# BlackIce-Nxt.net
KiCad netlist of a schematic drawn in EAGLE
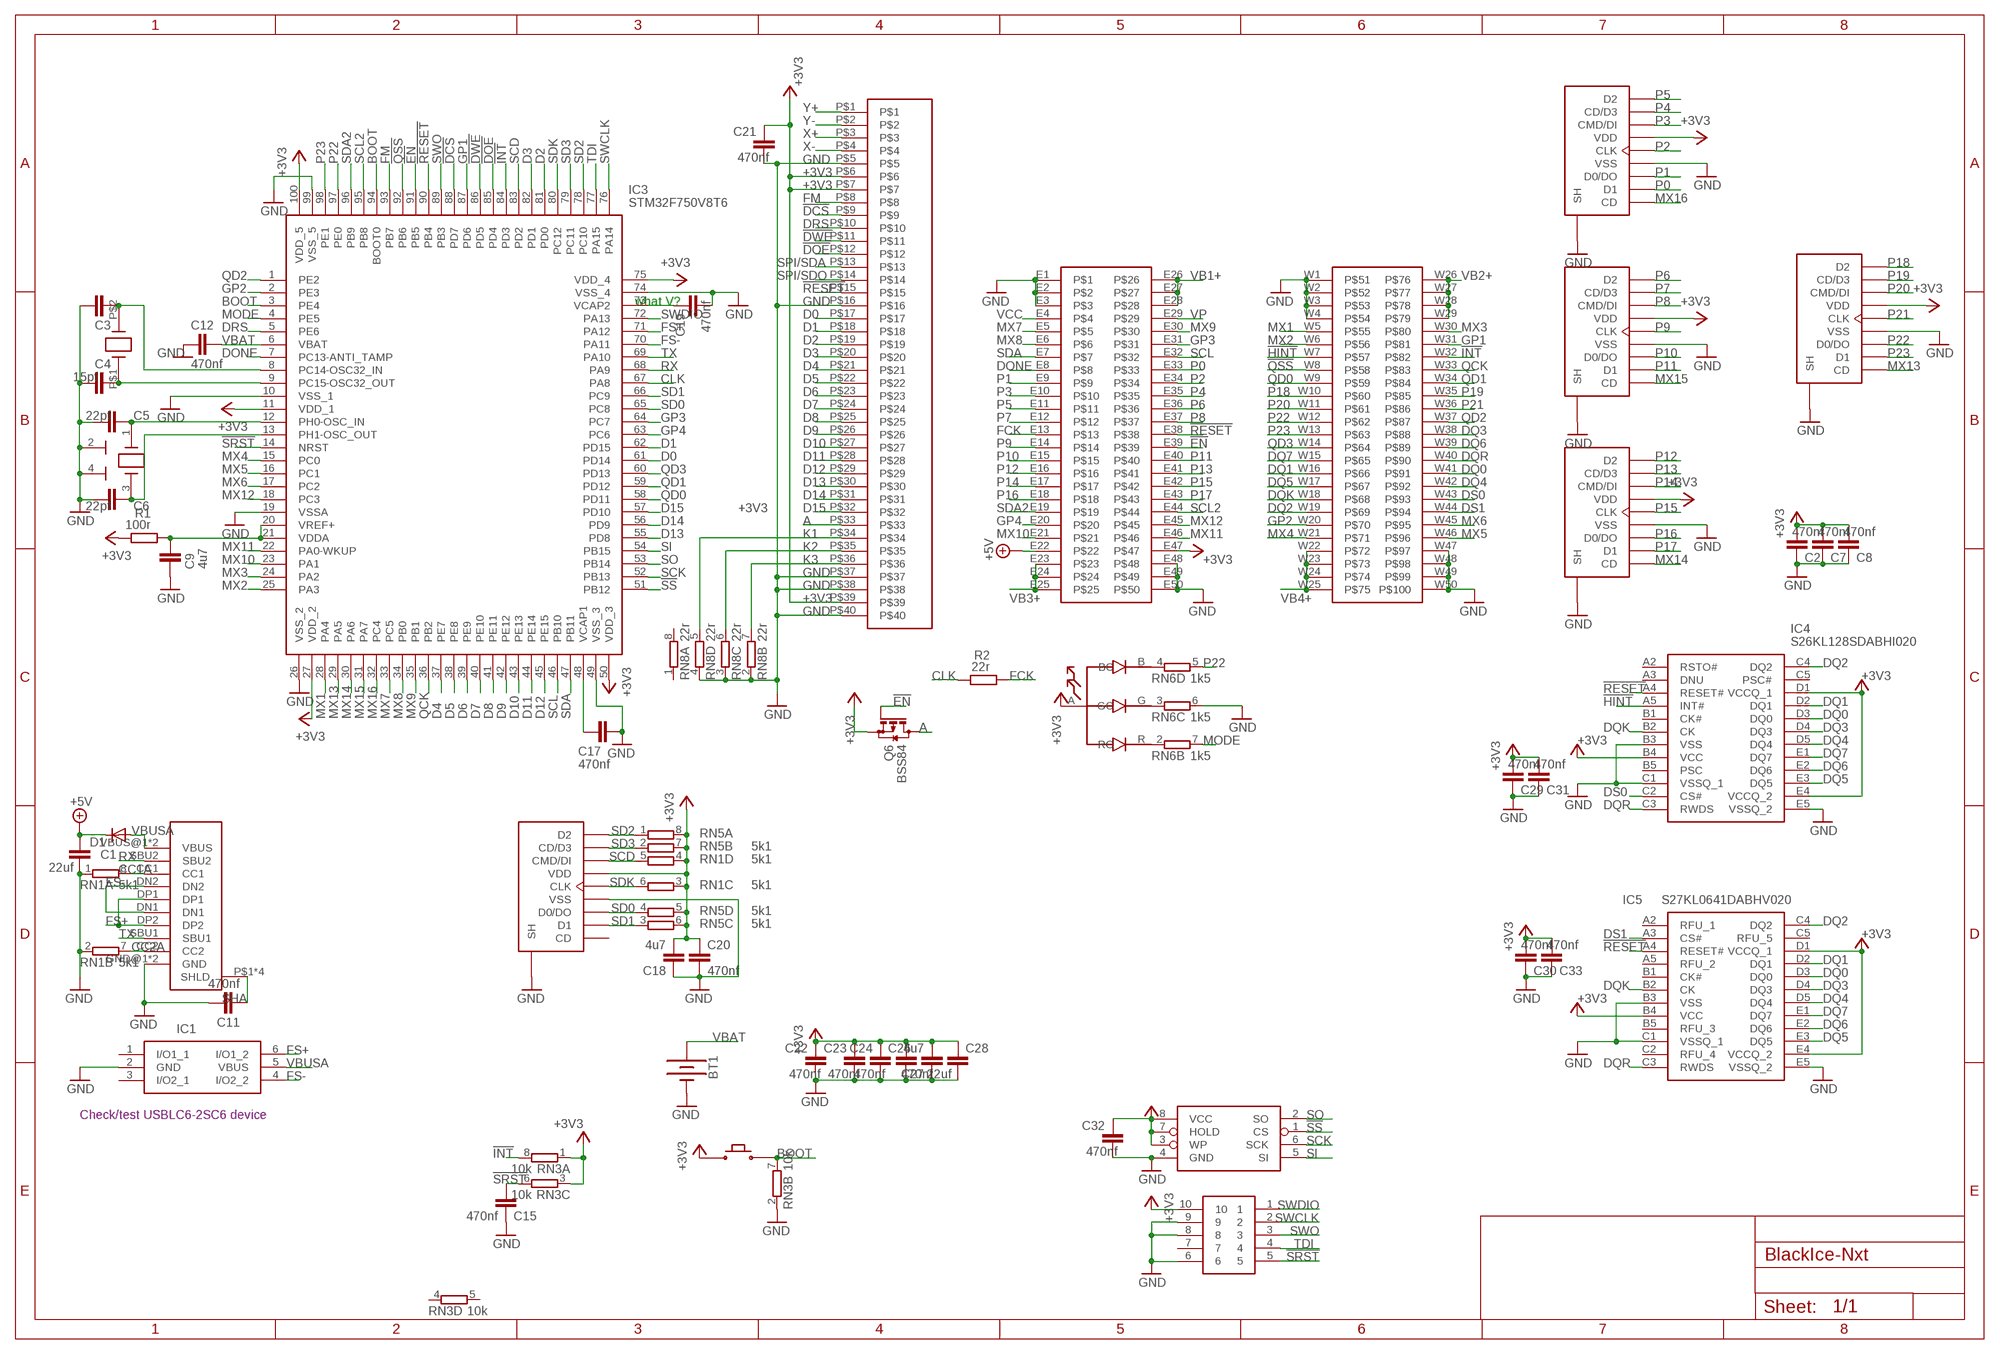
[diagram p0: schematic, sheet 1]

(export (version "E")
  (design (tool "Eeschema 10.0.6"))
  (components
    (comp (ref "B2")
      (value "4X3-RA-BUTTON")
      (footprint "eagle-import:4X3-RA-BUTTON")
      (libsource (lib "eagle-import") (part "4X3-RA-BUTTON"))
    )
    (comp (ref "BT1")
      (value "BATTERY-20MM_SMD")
      (footprint "eagle-import:BATTCON_20MM")
      (libsource (lib "eagle-import") (part "BATTERY-20MM_SMD"))
    )
    (comp (ref "C1")
      (value "22uf")
      (footprint "eagle-import:C0603")
      (libsource (lib "eagle-import") (part "C-EUC0603"))
    )
    (comp (ref "C2")
      (value "470nf")
      (footprint "eagle-import:C0402")
      (libsource (lib "eagle-import") (part "C-EUC0402"))
    )
    (comp (ref "C3")
      (value "15pf")
      (footprint "eagle-import:C0402")
      (libsource (lib "eagle-import") (part "C-EUC0402"))
    )
    (comp (ref "C4")
      (value "15pf")
      (footprint "eagle-import:C0402")
      (libsource (lib "eagle-import") (part "C-EUC0402"))
    )
    (comp (ref "C5")
      (value "22pf")
      (footprint "eagle-import:C0402")
      (libsource (lib "eagle-import") (part "C-EUC0402"))
    )
    (comp (ref "C6")
      (value "22pf")
      (footprint "eagle-import:C0402")
      (libsource (lib "eagle-import") (part "C-EUC0402"))
    )
    (comp (ref "C7")
      (value "470nf")
      (footprint "eagle-import:C0402")
      (libsource (lib "eagle-import") (part "C-EUC0402"))
    )
    (comp (ref "C8")
      (value "470nf")
      (footprint "eagle-import:C0402")
      (libsource (lib "eagle-import") (part "C-EUC0402"))
    )
    (comp (ref "C9")
      (value "4u7")
      (footprint "eagle-import:C0402")
      (libsource (lib "eagle-import") (part "C-EUC0402"))
    )
    (comp (ref "C10")
      (value "USB-C-16")
      (footprint "eagle-import:USB-C")
      (libsource (lib "eagle-import") (part "USB-C-16"))
    )
    (comp (ref "C11")
      (value "470nf")
      (footprint "eagle-import:C0402")
      (libsource (lib "eagle-import") (part "C-EUC0402"))
    )
    (comp (ref "C12")
      (value "470nf")
      (footprint "eagle-import:C0402")
      (libsource (lib "eagle-import") (part "C-EUC0402"))
    )
    (comp (ref "C15")
      (value "470nf")
      (footprint "eagle-import:C0402")
      (libsource (lib "eagle-import") (part "C-EUC0402"))
    )
    (comp (ref "C16")
      (value "TF-15X15")
      (footprint "eagle-import:SDCARD")
      (libsource (lib "eagle-import") (part "TF-15X15"))
    )
    (comp (ref "C17")
      (value "470nf")
      (footprint "eagle-import:C0402")
      (libsource (lib "eagle-import") (part "C-EUC0402"))
    )
    (comp (ref "C18")
      (value "4u7")
      (footprint "eagle-import:C0402")
      (libsource (lib "eagle-import") (part "C-EUC0402"))
    )
    (comp (ref "C19")
      (value "470nf")
      (footprint "eagle-import:C0402")
      (libsource (lib "eagle-import") (part "C-EUC0402"))
    )
    (comp (ref "C20")
      (value "470nf")
      (footprint "eagle-import:C0402")
      (libsource (lib "eagle-import") (part "C-EUC0402"))
    )
    (comp (ref "C21")
      (value "470nf")
      (footprint "eagle-import:C0402")
      (libsource (lib "eagle-import") (part "C-EUC0402"))
    )
    (comp (ref "C22")
      (value "470nf")
      (footprint "eagle-import:C0402")
      (libsource (lib "eagle-import") (part "C-EUC0402"))
    )
    (comp (ref "C23")
      (value "470nf")
      (footprint "eagle-import:C0402")
      (libsource (lib "eagle-import") (part "C-EUC0402"))
    )
    (comp (ref "C24")
      (value "470nf")
      (footprint "eagle-import:C0402")
      (libsource (lib "eagle-import") (part "C-EUC0402"))
    )
    (comp (ref "C25")
      (value "XF2M-4015-1AFPC-0.5")
      (footprint "eagle-import:XF2M-4015-1A")
      (libsource (lib "eagle-import") (part "XF2M-4015-1AFPC-0.5"))
    )
    (comp (ref "C26")
      (value "470nf")
      (footprint "eagle-import:C0402")
      (libsource (lib "eagle-import") (part "C-EUC0402"))
    )
    (comp (ref "C27")
      (value "4u7")
      (footprint "eagle-import:C0402")
      (libsource (lib "eagle-import") (part "C-EUC0402"))
    )
    (comp (ref "C28")
      (value "22uf")
      (footprint "eagle-import:C0603")
      (libsource (lib "eagle-import") (part "C-EUC0603"))
    )
    (comp (ref "C29")
      (value "470nf")
      (footprint "eagle-import:C0402")
      (libsource (lib "eagle-import") (part "C-EUC0402"))
    )
    (comp (ref "C30")
      (value "470nf")
      (footprint "eagle-import:C0402")
      (libsource (lib "eagle-import") (part "C-EUC0402"))
    )
    (comp (ref "C31")
      (value "470nf")
      (footprint "eagle-import:C0402")
      (libsource (lib "eagle-import") (part "C-EUC0402"))
    )
    (comp (ref "C32")
      (value "470nf")
      (footprint "eagle-import:C0402")
      (libsource (lib "eagle-import") (part "C-EUC0402"))
    )
    (comp (ref "C33")
      (value "470nf")
      (footprint "eagle-import:C0402")
      (libsource (lib "eagle-import") (part "C-EUC0402"))
    )
    (comp (ref "C34")
      (value "2X5-HEADER")
      (footprint "eagle-import:1.27-2X5-HEADER")
      (libsource (lib "eagle-import") (part "2X5-HEADER"))
    )
    (comp (ref "C35")
      (value "TF-15X15")
      (footprint "eagle-import:SDCARD")
      (libsource (lib "eagle-import") (part "TF-15X15"))
    )
    (comp (ref "C36")
      (value "TF-15X15")
      (footprint "eagle-import:SDCARD")
      (libsource (lib "eagle-import") (part "TF-15X15"))
    )
    (comp (ref "C38")
      (value "TF-15X15")
      (footprint "eagle-import:SDCARD")
      (libsource (lib "eagle-import") (part "TF-15X15"))
    )
    (comp (ref "C41")
      (value "TF-15X15")
      (footprint "eagle-import:SDCARD")
      (libsource (lib "eagle-import") (part "TF-15X15"))
    )
    (comp (ref "D1")
      (value "DIODE-SOD123")
      (footprint "eagle-import:SOD123")
      (libsource (lib "eagle-import") (part "DIODE-SOD123"))
    )
    (comp (ref "IC1")
      (value "USBLC6-2SC6")
      (footprint "eagle-import:SOT95P280X145-6N")
      (fields (field (name "MOUSER_PART_NUMBER") "511-USBLC6-2SC6"))
      (libsource (lib "eagle-import") (part "USBLC6-2SC6"))
    )
    (comp (ref "IC3")
      (value "STM32F750V8T6")
      (footprint "eagle-import:QFP50P1600X1600X160-100N")
      (fields (field (name "MOUSER_PART_NUMBER") "511-STM32F750V8T6"))
      (libsource (lib "eagle-import") (part "STM32F750V8T6"))
    )
    (comp (ref "IC4")
      (value "S26KL128SDABHI020")
      (footprint "eagle-import:BGA24C100P5X5_600X800X100")
      (fields (field (name "MOUSER_PART_NUMBER") "727-S26KL128SDABHI02"))
      (libsource (lib "eagle-import") (part "S26KL128SDABHI020"))
    )
    (comp (ref "IC5")
      (value "S27KL0641DABHV020")
      (footprint "eagle-import:BGA24C100P5X5_600X800X100")
      (fields (field (name "MOUSER_PART_NUMBER") "727-S27KL0641DABHV02"))
      (libsource (lib "eagle-import") (part "S27KL0641DABHV020"))
    )
    (comp (ref "IC6")
      (value "AT25SDF041A")
      (footprint "eagle-import:SOIC-8-NARROW")
      (libsource (lib "eagle-import") (part "AT25SDF041A"))
    )
    (comp (ref "L1")
      (value "RGB_LED")
      (footprint "eagle-import:RGB_LED_IMM")
      (libsource (lib "eagle-import") (part "RGB_LED"))
    )
    (comp (ref "Q6")
      (value "BSS84")
      (footprint "eagle-import:SOT23")
      (libsource (lib "eagle-import") (part "BSS84"))
    )
    (comp (ref "R1")
      (value "100r")
      (footprint "eagle-import:R0402")
      (libsource (lib "eagle-import") (part "R-EU_R0402"))
    )
    (comp (ref "R2")
      (value "22r")
      (footprint "eagle-import:R0402")
      (libsource (lib "eagle-import") (part "R-EU_R0402"))
    )
    (comp (ref "RN1")
      (value "5k1")
      (footprint "eagle-import:EXB38V")
      (libsource (lib "eagle-import") (part "4R-NEXB38V"))
    )
    (comp (ref "RN3")
      (value "10k")
      (footprint "eagle-import:EXB38V")
      (libsource (lib "eagle-import") (part "4R-NEXB38V"))
    )
    (comp (ref "RN5")
      (value "5k1")
      (footprint "eagle-import:EXB38V")
      (libsource (lib "eagle-import") (part "4R-NEXB38V"))
    )
    (comp (ref "RN6")
      (value "1k5")
      (footprint "eagle-import:EXB38V")
      (libsource (lib "eagle-import") (part "4R-NEXB38V"))
    )
    (comp (ref "RN8")
      (value "22r")
      (footprint "eagle-import:EXB38V")
      (libsource (lib "eagle-import") (part "4R-NEXB38V"))
    )
    (comp (ref "T1")
      (value "MEZZANINEM-TILE")
      (footprint "eagle-import:MEZZANINNE-T")
      (libsource (lib "eagle-import") (part "MEZZANINEM-TILE"))
    )
    (comp (ref "X1")
      (value "FC-135")
      (footprint "eagle-import:FC135")
      (libsource (lib "eagle-import") (part "FC-135"))
    )
    (comp (ref "X2")
      (value "12MZ")
      (footprint "eagle-import:CRYSTAL-3.2X2.5")
      (libsource (lib "eagle-import") (part "7M-25"))
    )
  )
  (nets
    (net (code "1") (name "+3V3") (class "Default")
      (node (ref "B2") (pin "P$1") (pinfunction "P$1_P$1") (pintype "passive"))
      (node (ref "C16") (pin "P$6") (pinfunction "VDD_P$6") (pintype "power_in"))
      (node (ref "C18") (pin "2") (pinfunction "2_2") (pintype "passive"))
      (node (ref "C2") (pin "2") (pinfunction "2_2") (pintype "passive"))
      (node (ref "C20") (pin "1") (pinfunction "1_1") (pintype "passive"))
      (node (ref "C21") (pin "1") (pinfunction "1_1") (pintype "passive"))
      (node (ref "C22") (pin "1") (pinfunction "1_1") (pintype "passive"))
      (node (ref "C23") (pin "1") (pinfunction "1_1") (pintype "passive"))
      (node (ref "C24") (pin "1") (pinfunction "1_1") (pintype "passive"))
      (node (ref "C25") (pin "P$39") (pinfunction "P$39_P$39") (pintype "bidirectional"))
      (node (ref "C25") (pin "P$6") (pinfunction "P$6_P$6") (pintype "bidirectional"))
      (node (ref "C25") (pin "P$7") (pinfunction "P$7_P$7") (pintype "bidirectional"))
      (node (ref "C26") (pin "2") (pinfunction "2_2") (pintype "passive"))
      (node (ref "C27") (pin "2") (pinfunction "2_2") (pintype "passive"))
      (node (ref "C28") (pin "1") (pinfunction "1_1") (pintype "passive"))
      (node (ref "C29") (pin "2") (pinfunction "2_2") (pintype "passive"))
      (node (ref "C30") (pin "2") (pinfunction "2_2") (pintype "passive"))
      (node (ref "C31") (pin "2") (pinfunction "2_2") (pintype "passive"))
      (node (ref "C32") (pin "1") (pinfunction "1_1") (pintype "passive"))
      (node (ref "C33") (pin "2") (pinfunction "2_2") (pintype "passive"))
      (node (ref "C34") (pin "10") (pinfunction "10_10") (pintype "bidirectional"))
      (node (ref "C35") (pin "P$6") (pinfunction "VDD_P$6") (pintype "power_in"))
      (node (ref "C36") (pin "P$6") (pinfunction "VDD_P$6") (pintype "power_in"))
      (node (ref "C38") (pin "P$6") (pinfunction "VDD_P$6") (pintype "power_in"))
      (node (ref "C41") (pin "P$6") (pinfunction "VDD_P$6") (pintype "power_in"))
      (node (ref "C7") (pin "2") (pinfunction "2_2") (pintype "passive"))
      (node (ref "C8") (pin "2") (pinfunction "2_2") (pintype "passive"))
      (node (ref "IC3") (pin "100") (pinfunction "VDD_5_100") (pintype "bidirectional"))
      (node (ref "IC3") (pin "11") (pinfunction "VDD_1_11") (pintype "bidirectional"))
      (node (ref "IC3") (pin "27") (pinfunction "VDD_2_27") (pintype "bidirectional"))
      (node (ref "IC3") (pin "50") (pinfunction "VDD_3_50") (pintype "bidirectional"))
      (node (ref "IC3") (pin "75") (pinfunction "VDD_4_75") (pintype "bidirectional"))
      (node (ref "IC4") (pin "B4") (pinfunction "VCC_B4") (pintype "bidirectional"))
      (node (ref "IC4") (pin "D1") (pinfunction "VCCQ_1_D1") (pintype "bidirectional"))
      (node (ref "IC4") (pin "E4") (pinfunction "VCCQ_2_E4") (pintype "bidirectional"))
      (node (ref "IC5") (pin "B4") (pinfunction "VCC_B4") (pintype "bidirectional"))
      (node (ref "IC5") (pin "D1") (pinfunction "VCCQ_1_D1") (pintype "bidirectional"))
      (node (ref "IC5") (pin "E4") (pinfunction "VCCQ_2_E4") (pintype "bidirectional"))
      (node (ref "IC6") (pin "3") (pinfunction "WP_3") (pintype "bidirectional"))
      (node (ref "IC6") (pin "7") (pinfunction "HOLD_7") (pintype "bidirectional"))
      (node (ref "IC6") (pin "8") (pinfunction "VCC_8") (pintype "power_in"))
      (node (ref "L1") (pin "A") (pinfunction "ANODE_A") (pintype "bidirectional"))
      (node (ref "Q6") (pin "2") (pinfunction "S_2") (pintype "passive"))
      (node (ref "R1") (pin "2") (pinfunction "2_2") (pintype "passive"))
      (node (ref "RN1") (pin "3") (pinfunction "1_3") (pintype "passive"))
      (node (ref "RN1") (pin "4") (pinfunction "1_4") (pintype "passive"))
      (node (ref "RN3") (pin "1") (pinfunction "1_1") (pintype "passive"))
      (node (ref "RN3") (pin "3") (pinfunction "1_3") (pintype "passive"))
      (node (ref "RN5") (pin "5") (pinfunction "2_5") (pintype "passive"))
      (node (ref "RN5") (pin "6") (pinfunction "2_6") (pintype "passive"))
      (node (ref "RN5") (pin "7") (pinfunction "2_7") (pintype "passive"))
      (node (ref "RN5") (pin "8") (pinfunction "2_8") (pintype "passive"))
      (node (ref "T1") (pin "E47") (pinfunction "P$47_E47") (pintype "bidirectional"))
    )
    (net (code "2") (name "+5V") (class "Default")
      (node (ref "C1") (pin "1") (pinfunction "1_1") (pintype "passive"))
      (node (ref "D1") (pin "C") (pinfunction "C_C") (pintype "passive"))
      (node (ref "T1") (pin "E22") (pinfunction "P$22_E22") (pintype "bidirectional"))
    )
    (net (code "3") (name "/A") (class "Default")
      (node (ref "C25") (pin "P$33") (pinfunction "P$33_P$33") (pintype "bidirectional"))
      (node (ref "Q6") (pin "3") (pinfunction "D_3") (pintype "passive"))
    )
    (net (code "4") (name "/BOOT") (class "Default")
      (node (ref "B2") (pin "P$2") (pinfunction "P$2_P$2") (pintype "passive"))
      (node (ref "IC3") (pin "3") (pinfunction "PE4_3") (pintype "bidirectional"))
      (node (ref "IC3") (pin "94") (pinfunction "BOOT0_94") (pintype "bidirectional"))
      (node (ref "RN3") (pin "7") (pinfunction "2_7") (pintype "passive"))
    )
    (net (code "5") (name "/CC1A") (class "Default")
      (node (ref "C10") (pin "CC1") (pinfunction "CC1_CC1") (pintype "bidirectional"))
      (node (ref "RN1") (pin "8") (pinfunction "2_8") (pintype "passive"))
    )
    (net (code "6") (name "/CC2A") (class "Default")
      (node (ref "C10") (pin "CC2") (pinfunction "CC2_CC2") (pintype "bidirectional"))
      (node (ref "RN1") (pin "7") (pinfunction "2_7") (pintype "passive"))
    )
    (net (code "7") (name "/CLK") (class "Default")
      (node (ref "IC3") (pin "67") (pinfunction "PA8_67") (pintype "bidirectional"))
      (node (ref "R2") (pin "2") (pinfunction "2_2") (pintype "passive"))
    )
    (net (code "8") (name "/D0") (class "Default")
      (node (ref "C25") (pin "P$17") (pinfunction "P$17_P$17") (pintype "bidirectional"))
      (node (ref "IC3") (pin "61") (pinfunction "PD14_61") (pintype "bidirectional"))
    )
    (net (code "9") (name "/D1") (class "Default")
      (node (ref "C25") (pin "P$18") (pinfunction "P$18_P$18") (pintype "bidirectional"))
      (node (ref "IC3") (pin "62") (pinfunction "PD15_62") (pintype "bidirectional"))
    )
    (net (code "10") (name "/D2") (class "Default")
      (node (ref "C25") (pin "P$19") (pinfunction "P$19_P$19") (pintype "bidirectional"))
      (node (ref "IC3") (pin "81") (pinfunction "PD0_81") (pintype "bidirectional"))
    )
    (net (code "11") (name "/D3") (class "Default")
      (node (ref "C25") (pin "P$20") (pinfunction "P$20_P$20") (pintype "bidirectional"))
      (node (ref "IC3") (pin "82") (pinfunction "PD1_82") (pintype "bidirectional"))
    )
    (net (code "12") (name "/D4") (class "Default")
      (node (ref "C25") (pin "P$21") (pinfunction "P$21_P$21") (pintype "bidirectional"))
      (node (ref "IC3") (pin "37") (pinfunction "PE7_37") (pintype "bidirectional"))
    )
    (net (code "13") (name "/D5") (class "Default")
      (node (ref "C25") (pin "P$22") (pinfunction "P$22_P$22") (pintype "bidirectional"))
      (node (ref "IC3") (pin "38") (pinfunction "PE8_38") (pintype "bidirectional"))
    )
    (net (code "14") (name "/D6") (class "Default")
      (node (ref "C25") (pin "P$23") (pinfunction "P$23_P$23") (pintype "bidirectional"))
      (node (ref "IC3") (pin "39") (pinfunction "PE9_39") (pintype "bidirectional"))
    )
    (net (code "15") (name "/D7") (class "Default")
      (node (ref "C25") (pin "P$24") (pinfunction "P$24_P$24") (pintype "bidirectional"))
      (node (ref "IC3") (pin "40") (pinfunction "PE10_40") (pintype "bidirectional"))
    )
    (net (code "16") (name "/D8") (class "Default")
      (node (ref "C25") (pin "P$25") (pinfunction "P$25_P$25") (pintype "bidirectional"))
      (node (ref "IC3") (pin "41") (pinfunction "PE11_41") (pintype "bidirectional"))
    )
    (net (code "17") (name "/D9") (class "Default")
      (node (ref "C25") (pin "P$26") (pinfunction "P$26_P$26") (pintype "bidirectional"))
      (node (ref "IC3") (pin "42") (pinfunction "PE12_42") (pintype "bidirectional"))
    )
    (net (code "18") (name "/D10") (class "Default")
      (node (ref "C25") (pin "P$27") (pinfunction "P$27_P$27") (pintype "bidirectional"))
      (node (ref "IC3") (pin "43") (pinfunction "PE13_43") (pintype "bidirectional"))
    )
    (net (code "19") (name "/D11") (class "Default")
      (node (ref "C25") (pin "P$28") (pinfunction "P$28_P$28") (pintype "bidirectional"))
      (node (ref "IC3") (pin "44") (pinfunction "PE14_44") (pintype "bidirectional"))
    )
    (net (code "20") (name "/D12") (class "Default")
      (node (ref "C25") (pin "P$29") (pinfunction "P$29_P$29") (pintype "bidirectional"))
      (node (ref "IC3") (pin "45") (pinfunction "PE15_45") (pintype "bidirectional"))
    )
    (net (code "21") (name "/D13") (class "Default")
      (node (ref "C25") (pin "P$30") (pinfunction "P$30_P$30") (pintype "bidirectional"))
      (node (ref "IC3") (pin "55") (pinfunction "PD8_55") (pintype "bidirectional"))
    )
    (net (code "22") (name "/D14") (class "Default")
      (node (ref "C25") (pin "P$31") (pinfunction "P$31_P$31") (pintype "bidirectional"))
      (node (ref "IC3") (pin "56") (pinfunction "PD9_56") (pintype "bidirectional"))
    )
    (net (code "23") (name "/D15") (class "Default")
      (node (ref "C25") (pin "P$32") (pinfunction "P$32_P$32") (pintype "bidirectional"))
      (node (ref "IC3") (pin "57") (pinfunction "PD10_57") (pintype "bidirectional"))
    )
    (net (code "24") (name "/DONE") (class "Default")
      (node (ref "IC3") (pin "7") (pinfunction "PC13-ANTI_TAMP_7") (pintype "bidirectional"))
      (node (ref "T1") (pin "E8") (pinfunction "P$8_E8") (pintype "bidirectional"))
    )
    (net (code "25") (name "/DQ0") (class "Default")
      (node (ref "IC4") (pin "D3") (pinfunction "DQ0_D3") (pintype "bidirectional"))
      (node (ref "IC5") (pin "D3") (pinfunction "DQ0_D3") (pintype "bidirectional"))
      (node (ref "T1") (pin "W41") (pinfunction "P$91_W41") (pintype "bidirectional"))
    )
    (net (code "26") (name "/DQ1") (class "Default")
      (node (ref "IC4") (pin "D2") (pinfunction "DQ1_D2") (pintype "bidirectional"))
      (node (ref "IC5") (pin "D2") (pinfunction "DQ1_D2") (pintype "bidirectional"))
      (node (ref "T1") (pin "W16") (pinfunction "P$66_W16") (pintype "bidirectional"))
    )
    (net (code "27") (name "/DQ2") (class "Default")
      (node (ref "IC4") (pin "C4") (pinfunction "DQ2_C4") (pintype "bidirectional"))
      (node (ref "IC5") (pin "C4") (pinfunction "DQ2_C4") (pintype "bidirectional"))
      (node (ref "T1") (pin "W19") (pinfunction "P$69_W19") (pintype "bidirectional"))
    )
    (net (code "28") (name "/DQ3") (class "Default")
      (node (ref "IC4") (pin "D4") (pinfunction "DQ3_D4") (pintype "bidirectional"))
      (node (ref "IC5") (pin "D4") (pinfunction "DQ3_D4") (pintype "bidirectional"))
      (node (ref "T1") (pin "W38") (pinfunction "P$88_W38") (pintype "bidirectional"))
    )
    (net (code "29") (name "/DQ4") (class "Default")
      (node (ref "IC4") (pin "D5") (pinfunction "DQ4_D5") (pintype "bidirectional"))
      (node (ref "IC5") (pin "D5") (pinfunction "DQ4_D5") (pintype "bidirectional"))
      (node (ref "T1") (pin "W42") (pinfunction "P$92_W42") (pintype "bidirectional"))
    )
    (net (code "30") (name "/DQ5") (class "Default")
      (node (ref "IC4") (pin "E3") (pinfunction "DQ5_E3") (pintype "bidirectional"))
      (node (ref "IC5") (pin "E3") (pinfunction "DQ5_E3") (pintype "bidirectional"))
      (node (ref "T1") (pin "W17") (pinfunction "P$67_W17") (pintype "bidirectional"))
    )
    (net (code "31") (name "/DQ6") (class "Default")
      (node (ref "IC4") (pin "E2") (pinfunction "DQ6_E2") (pintype "bidirectional"))
      (node (ref "IC5") (pin "E2") (pinfunction "DQ6_E2") (pintype "bidirectional"))
      (node (ref "T1") (pin "W39") (pinfunction "P$89_W39") (pintype "bidirectional"))
    )
    (net (code "32") (name "/DQ7") (class "Default")
      (node (ref "IC4") (pin "E1") (pinfunction "DQ7_E1") (pintype "bidirectional"))
      (node (ref "IC5") (pin "E1") (pinfunction "DQ7_E1") (pintype "bidirectional"))
      (node (ref "T1") (pin "W15") (pinfunction "P$65_W15") (pintype "bidirectional"))
    )
    (net (code "33") (name "/DQK") (class "Default")
      (node (ref "IC4") (pin "B2") (pinfunction "CK_B2") (pintype "bidirectional"))
      (node (ref "IC5") (pin "B2") (pinfunction "CK_B2") (pintype "bidirectional"))
      (node (ref "T1") (pin "W18") (pinfunction "P$68_W18") (pintype "bidirectional"))
    )
    (net (code "34") (name "/DQR") (class "Default")
      (node (ref "IC4") (pin "C3") (pinfunction "RWDS_C3") (pintype "bidirectional"))
      (node (ref "IC5") (pin "C3") (pinfunction "RWDS_C3") (pintype "bidirectional"))
      (node (ref "T1") (pin "W40") (pinfunction "P$90_W40") (pintype "bidirectional"))
    )
    (net (code "35") (name "/DRS") (class "Default")
      (node (ref "C25") (pin "P$10") (pinfunction "P$10_P$10") (pintype "bidirectional"))
      (node (ref "IC3") (pin "5") (pinfunction "PE6_5") (pintype "bidirectional"))
    )
    (net (code "36") (name "/DS0") (class "Default")
      (node (ref "IC4") (pin "C2") (pinfunction "CS#_C2") (pintype "bidirectional"))
      (node (ref "T1") (pin "W43") (pinfunction "P$93_W43") (pintype "bidirectional"))
    )
    (net (code "37") (name "/DS1") (class "Default")
      (node (ref "IC5") (pin "A3") (pinfunction "CS#_A3") (pintype "bidirectional"))
      (node (ref "T1") (pin "W44") (pinfunction "P$94_W44") (pintype "bidirectional"))
    )
    (net (code "38") (name "/FCK") (class "Default")
      (node (ref "R2") (pin "1") (pinfunction "1_1") (pintype "passive"))
      (node (ref "T1") (pin "E13") (pinfunction "P$13_E13") (pintype "bidirectional"))
    )
    (net (code "39") (name "/FM") (class "Default")
      (node (ref "C25") (pin "P$8") (pinfunction "P$8_P$8") (pintype "bidirectional"))
      (node (ref "IC3") (pin "93") (pinfunction "PB7_93") (pintype "bidirectional"))
    )
    (net (code "40") (name "/FS+") (class "Default")
      (node (ref "C10") (pin "DP1") (pinfunction "DP1_DP1") (pintype "bidirectional"))
      (node (ref "C10") (pin "DP2") (pinfunction "DP2_DP2") (pintype "bidirectional"))
      (node (ref "IC1") (pin "6") (pinfunction "I/O1_2_6") (pintype "bidirectional"))
      (node (ref "IC3") (pin "71") (pinfunction "PA12_71") (pintype "bidirectional"))
    )
    (net (code "41") (name "/FS-") (class "Default")
      (node (ref "C10") (pin "DN1") (pinfunction "DN1_DN1") (pintype "bidirectional"))
      (node (ref "C10") (pin "DN2") (pinfunction "DN2_DN2") (pintype "bidirectional"))
      (node (ref "IC1") (pin "4") (pinfunction "I/O2_2_4") (pintype "bidirectional"))
      (node (ref "IC3") (pin "70") (pinfunction "PA11_70") (pintype "bidirectional"))
    )
    (net (code "42") (name "/GP1") (class "Default")
      (node (ref "IC3") (pin "87") (pinfunction "PD6_87") (pintype "bidirectional"))
      (node (ref "T1") (pin "W31") (pinfunction "P$81_W31") (pintype "bidirectional"))
    )
    (net (code "43") (name "/GP2") (class "Default")
      (node (ref "IC3") (pin "2") (pinfunction "PE3_2") (pintype "bidirectional"))
      (node (ref "T1") (pin "W20") (pinfunction "P$70_W20") (pintype "bidirectional"))
    )
    (net (code "44") (name "/GP3") (class "Default")
      (node (ref "IC3") (pin "64") (pinfunction "PC7_64") (pintype "bidirectional"))
      (node (ref "T1") (pin "E31") (pinfunction "P$31_E31") (pintype "bidirectional"))
    )
    (net (code "45") (name "/GP4") (class "Default")
      (node (ref "IC3") (pin "63") (pinfunction "PC6_63") (pintype "bidirectional"))
      (node (ref "T1") (pin "E20") (pinfunction "P$20_E20") (pintype "bidirectional"))
    )
    (net (code "46") (name "/K1") (class "Default")
      (node (ref "C25") (pin "P$34") (pinfunction "P$34_P$34") (pintype "bidirectional"))
      (node (ref "RN8") (pin "5") (pinfunction "2_5") (pintype "passive"))
    )
    (net (code "47") (name "/K2") (class "Default")
      (node (ref "C25") (pin "P$35") (pinfunction "P$35_P$35") (pintype "bidirectional"))
      (node (ref "RN8") (pin "6") (pinfunction "2_6") (pintype "passive"))
    )
    (net (code "48") (name "/K3") (class "Default")
      (node (ref "C25") (pin "P$36") (pinfunction "P$36_P$36") (pintype "bidirectional"))
      (node (ref "RN8") (pin "7") (pinfunction "2_7") (pintype "passive"))
    )
    (net (code "49") (name "/MODE") (class "Default")
      (node (ref "IC3") (pin "4") (pinfunction "PE5_4") (pintype "bidirectional"))
      (node (ref "RN6") (pin "7") (pinfunction "2_7") (pintype "passive"))
    )
    (net (code "50") (name "/MX1") (class "Default")
      (node (ref "IC3") (pin "28") (pinfunction "PA4_28") (pintype "bidirectional"))
      (node (ref "T1") (pin "W5") (pinfunction "P$55_W5") (pintype "bidirectional"))
    )
    (net (code "51") (name "/MX2") (class "Default")
      (node (ref "IC3") (pin "25") (pinfunction "PA3_25") (pintype "bidirectional"))
      (node (ref "T1") (pin "W6") (pinfunction "P$56_W6") (pintype "bidirectional"))
    )
    (net (code "52") (name "/MX3") (class "Default")
      (node (ref "IC3") (pin "24") (pinfunction "PA2_24") (pintype "bidirectional"))
      (node (ref "T1") (pin "W30") (pinfunction "P$80_W30") (pintype "bidirectional"))
    )
    (net (code "53") (name "/MX4") (class "Default")
      (node (ref "IC3") (pin "15") (pinfunction "PC0_15") (pintype "bidirectional"))
      (node (ref "T1") (pin "W21") (pinfunction "P$71_W21") (pintype "bidirectional"))
    )
    (net (code "54") (name "/MX5") (class "Default")
      (node (ref "IC3") (pin "16") (pinfunction "PC1_16") (pintype "bidirectional"))
      (node (ref "T1") (pin "W46") (pinfunction "P$96_W46") (pintype "bidirectional"))
    )
    (net (code "55") (name "/MX6") (class "Default")
      (node (ref "IC3") (pin "17") (pinfunction "PC2_17") (pintype "bidirectional"))
      (node (ref "T1") (pin "W45") (pinfunction "P$95_W45") (pintype "bidirectional"))
    )
    (net (code "56") (name "/MX7") (class "Default")
      (node (ref "IC3") (pin "33") (pinfunction "PC5_33") (pintype "bidirectional"))
      (node (ref "T1") (pin "E5") (pinfunction "P$5_E5") (pintype "bidirectional"))
    )
    (net (code "57") (name "/MX8") (class "Default")
      (node (ref "IC3") (pin "34") (pinfunction "PB0_34") (pintype "bidirectional"))
      (node (ref "T1") (pin "E6") (pinfunction "P$6_E6") (pintype "bidirectional"))
    )
    (net (code "58") (name "/MX9") (class "Default")
      (node (ref "IC3") (pin "35") (pinfunction "PB1_35") (pintype "bidirectional"))
      (node (ref "T1") (pin "E30") (pinfunction "P$30_E30") (pintype "bidirectional"))
    )
    (net (code "59") (name "/MX10") (class "Default")
      (node (ref "IC3") (pin "23") (pinfunction "PA1_23") (pintype "bidirectional"))
      (node (ref "T1") (pin "E21") (pinfunction "P$21_E21") (pintype "bidirectional"))
    )
    (net (code "60") (name "/MX11") (class "Default")
      (node (ref "IC3") (pin "22") (pinfunction "PA0-WKUP_22") (pintype "bidirectional"))
      (node (ref "T1") (pin "E46") (pinfunction "P$46_E46") (pintype "bidirectional"))
    )
    (net (code "61") (name "/MX12") (class "Default")
      (node (ref "IC3") (pin "18") (pinfunction "PC3_18") (pintype "bidirectional"))
      (node (ref "T1") (pin "E45") (pinfunction "P$45_E45") (pintype "bidirectional"))
    )
    (net (code "62") (name "/MX13") (class "Default")
      (node (ref "C41") (pin "P$1") (pinfunction "CD_P$1") (pintype "bidirectional"))
      (node (ref "IC3") (pin "29") (pinfunction "PA5_29") (pintype "bidirectional"))
    )
    (net (code "63") (name "/MX14") (class "Default")
      (node (ref "C36") (pin "P$1") (pinfunction "CD_P$1") (pintype "bidirectional"))
      (node (ref "IC3") (pin "30") (pinfunction "PA6_30") (pintype "bidirectional"))
    )
    (net (code "64") (name "/MX15") (class "Default")
      (node (ref "C38") (pin "P$1") (pinfunction "CD_P$1") (pintype "bidirectional"))
      (node (ref "IC3") (pin "31") (pinfunction "PA7_31") (pintype "bidirectional"))
    )
    (net (code "65") (name "/MX16") (class "Default")
      (node (ref "C35") (pin "P$1") (pinfunction "CD_P$1") (pintype "bidirectional"))
      (node (ref "IC3") (pin "32") (pinfunction "PC4_32") (pintype "bidirectional"))
    )
    (net (code "66") (name "/P0") (class "Default")
      (node (ref "C35") (pin "P$2") (pinfunction "D1_P$2") (pintype "bidirectional"))
      (node (ref "T1") (pin "E33") (pinfunction "P$33_E33") (pintype "bidirectional"))
    )
    (net (code "67") (name "/P1") (class "Default")
      (node (ref "C35") (pin "P$3") (pinfunction "D0/DO_P$3") (pintype "bidirectional"))
      (node (ref "T1") (pin "E9") (pinfunction "P$9_E9") (pintype "bidirectional"))
    )
    (net (code "68") (name "/P2") (class "Default")
      (node (ref "C35") (pin "P$5") (pinfunction "CLK_P$5") (pintype "bidirectional"))
      (node (ref "T1") (pin "E34") (pinfunction "P$34_E34") (pintype "bidirectional"))
    )
    (net (code "69") (name "/P3") (class "Default")
      (node (ref "C35") (pin "P$7") (pinfunction "CMD/DI_P$7") (pintype "bidirectional"))
      (node (ref "T1") (pin "E10") (pinfunction "P$10_E10") (pintype "bidirectional"))
    )
    (net (code "70") (name "/P4") (class "Default")
      (node (ref "C35") (pin "P$8") (pinfunction "CD/D3_P$8") (pintype "bidirectional"))
      (node (ref "T1") (pin "E35") (pinfunction "P$35_E35") (pintype "bidirectional"))
    )
    (net (code "71") (name "/P5") (class "Default")
      (node (ref "C35") (pin "P$9") (pinfunction "D2_P$9") (pintype "bidirectional"))
      (node (ref "T1") (pin "E11") (pinfunction "P$11_E11") (pintype "bidirectional"))
    )
    (net (code "72") (name "/P6") (class "Default")
      (node (ref "C38") (pin "P$9") (pinfunction "D2_P$9") (pintype "bidirectional"))
      (node (ref "T1") (pin "E36") (pinfunction "P$36_E36") (pintype "bidirectional"))
    )
    (net (code "73") (name "/P7") (class "Default")
      (node (ref "C38") (pin "P$8") (pinfunction "CD/D3_P$8") (pintype "bidirectional"))
      (node (ref "T1") (pin "E12") (pinfunction "P$12_E12") (pintype "bidirectional"))
    )
    (net (code "74") (name "/P8") (class "Default")
      (node (ref "C38") (pin "P$7") (pinfunction "CMD/DI_P$7") (pintype "bidirectional"))
      (node (ref "T1") (pin "E37") (pinfunction "P$37_E37") (pintype "bidirectional"))
    )
    (net (code "75") (name "/P9") (class "Default")
      (node (ref "C38") (pin "P$5") (pinfunction "CLK_P$5") (pintype "bidirectional"))
      (node (ref "T1") (pin "E14") (pinfunction "P$14_E14") (pintype "bidirectional"))
    )
    (net (code "76") (name "/P10") (class "Default")
      (node (ref "C38") (pin "P$3") (pinfunction "D0/DO_P$3") (pintype "bidirectional"))
      (node (ref "T1") (pin "E15") (pinfunction "P$15_E15") (pintype "bidirectional"))
    )
    (net (code "77") (name "/P11") (class "Default")
      (node (ref "C38") (pin "P$2") (pinfunction "D1_P$2") (pintype "bidirectional"))
      (node (ref "T1") (pin "E40") (pinfunction "P$40_E40") (pintype "bidirectional"))
    )
    (net (code "78") (name "/P12") (class "Default")
      (node (ref "C36") (pin "P$9") (pinfunction "D2_P$9") (pintype "bidirectional"))
      (node (ref "T1") (pin "E16") (pinfunction "P$16_E16") (pintype "bidirectional"))
    )
    (net (code "79") (name "/P13") (class "Default")
      (node (ref "C36") (pin "P$8") (pinfunction "CD/D3_P$8") (pintype "bidirectional"))
      (node (ref "T1") (pin "E41") (pinfunction "P$41_E41") (pintype "bidirectional"))
    )
    (net (code "80") (name "/P14") (class "Default")
      (node (ref "C36") (pin "P$7") (pinfunction "CMD/DI_P$7") (pintype "bidirectional"))
      (node (ref "T1") (pin "E17") (pinfunction "P$17_E17") (pintype "bidirectional"))
    )
    (net (code "81") (name "/P15") (class "Default")
      (node (ref "C36") (pin "P$5") (pinfunction "CLK_P$5") (pintype "bidirectional"))
      (node (ref "T1") (pin "E42") (pinfunction "P$42_E42") (pintype "bidirectional"))
    )
    (net (code "82") (name "/P16") (class "Default")
      (node (ref "C36") (pin "P$3") (pinfunction "D0/DO_P$3") (pintype "bidirectional"))
      (node (ref "T1") (pin "E18") (pinfunction "P$18_E18") (pintype "bidirectional"))
    )
    (net (code "83") (name "/P17") (class "Default")
      (node (ref "C36") (pin "P$2") (pinfunction "D1_P$2") (pintype "bidirectional"))
      (node (ref "T1") (pin "E43") (pinfunction "P$43_E43") (pintype "bidirectional"))
    )
    (net (code "84") (name "/P18") (class "Default")
      (node (ref "C41") (pin "P$9") (pinfunction "D2_P$9") (pintype "bidirectional"))
      (node (ref "T1") (pin "W10") (pinfunction "P$60_W10") (pintype "bidirectional"))
    )
    (net (code "85") (name "/P19") (class "Default")
      (node (ref "C41") (pin "P$8") (pinfunction "CD/D3_P$8") (pintype "bidirectional"))
      (node (ref "T1") (pin "W35") (pinfunction "P$85_W35") (pintype "bidirectional"))
    )
    (net (code "86") (name "/P20") (class "Default")
      (node (ref "C41") (pin "P$7") (pinfunction "CMD/DI_P$7") (pintype "bidirectional"))
      (node (ref "T1") (pin "W11") (pinfunction "P$61_W11") (pintype "bidirectional"))
    )
    (net (code "87") (name "/P21") (class "Default")
      (node (ref "C41") (pin "P$5") (pinfunction "CLK_P$5") (pintype "bidirectional"))
      (node (ref "T1") (pin "W36") (pinfunction "P$86_W36") (pintype "bidirectional"))
    )
    (net (code "88") (name "/P22") (class "Default")
      (node (ref "C41") (pin "P$3") (pinfunction "D0/DO_P$3") (pintype "bidirectional"))
      (node (ref "IC3") (pin "97") (pinfunction "PE0_97") (pintype "bidirectional"))
      (node (ref "RN6") (pin "5") (pinfunction "2_5") (pintype "passive"))
      (node (ref "T1") (pin "W12") (pinfunction "P$62_W12") (pintype "bidirectional"))
    )
    (net (code "89") (name "/P23") (class "Default")
      (node (ref "C41") (pin "P$2") (pinfunction "D1_P$2") (pintype "bidirectional"))
      (node (ref "IC3") (pin "98") (pinfunction "PE1_98") (pintype "bidirectional"))
      (node (ref "T1") (pin "W13") (pinfunction "P$63_W13") (pintype "bidirectional"))
    )
    (net (code "90") (name "/QCK") (class "Default")
      (node (ref "IC3") (pin "36") (pinfunction "PB2_36") (pintype "bidirectional"))
      (node (ref "T1") (pin "W33") (pinfunction "P$83_W33") (pintype "bidirectional"))
    )
    (net (code "91") (name "/QD0") (class "Default")
      (node (ref "IC3") (pin "58") (pinfunction "PD11_58") (pintype "bidirectional"))
      (node (ref "T1") (pin "W9") (pinfunction "P$59_W9") (pintype "bidirectional"))
    )
    (net (code "92") (name "/QD1") (class "Default")
      (node (ref "IC3") (pin "59") (pinfunction "PD12_59") (pintype "bidirectional"))
      (node (ref "T1") (pin "W34") (pinfunction "P$84_W34") (pintype "bidirectional"))
    )
    (net (code "93") (name "/QD2") (class "Default")
      (node (ref "IC3") (pin "1") (pinfunction "PE2_1") (pintype "bidirectional"))
      (node (ref "T1") (pin "W37") (pinfunction "P$87_W37") (pintype "bidirectional"))
    )
    (net (code "94") (name "/QD3") (class "Default")
      (node (ref "IC3") (pin "60") (pinfunction "PD13_60") (pintype "bidirectional"))
      (node (ref "T1") (pin "W14") (pinfunction "P$64_W14") (pintype "bidirectional"))
    )
    (net (code "95") (name "/RX") (class "Default")
      (node (ref "C10") (pin "SBU2") (pinfunction "SBU2_SBU2") (pintype "bidirectional"))
      (node (ref "IC3") (pin "68") (pinfunction "PA9_68") (pintype "bidirectional"))
    )
    (net (code "96") (name "/SCD") (class "Default")
      (node (ref "C16") (pin "P$7") (pinfunction "CMD/DI_P$7") (pintype "bidirectional"))
      (node (ref "IC3") (pin "83") (pinfunction "PD2_83") (pintype "bidirectional"))
      (node (ref "RN1") (pin "5") (pinfunction "2_5") (pintype "passive"))
    )
    (net (code "97") (name "/SCK") (class "Default")
      (node (ref "IC3") (pin "52") (pinfunction "PB13_52") (pintype "bidirectional"))
      (node (ref "IC6") (pin "6") (pinfunction "SCK_6") (pintype "bidirectional"))
    )
    (net (code "98") (name "/SCL") (class "Default")
      (node (ref "IC3") (pin "46") (pinfunction "PB10_46") (pintype "bidirectional"))
      (node (ref "T1") (pin "E32") (pinfunction "P$32_E32") (pintype "bidirectional"))
    )
    (net (code "99") (name "/SCL2") (class "Default")
      (node (ref "IC3") (pin "95") (pinfunction "PB8_95") (pintype "bidirectional"))
      (node (ref "T1") (pin "E44") (pinfunction "P$44_E44") (pintype "bidirectional"))
    )
    (net (code "100") (name "/SD0") (class "Default")
      (node (ref "C16") (pin "P$3") (pinfunction "D0/DO_P$3") (pintype "bidirectional"))
      (node (ref "IC3") (pin "65") (pinfunction "PC8_65") (pintype "bidirectional"))
      (node (ref "RN5") (pin "4") (pinfunction "1_4") (pintype "passive"))
    )
    (net (code "101") (name "/SD1") (class "Default")
      (node (ref "C16") (pin "P$2") (pinfunction "D1_P$2") (pintype "bidirectional"))
      (node (ref "IC3") (pin "66") (pinfunction "PC9_66") (pintype "bidirectional"))
      (node (ref "RN5") (pin "3") (pinfunction "1_3") (pintype "passive"))
    )
    (net (code "102") (name "/SD2") (class "Default")
      (node (ref "C16") (pin "P$9") (pinfunction "D2_P$9") (pintype "bidirectional"))
      (node (ref "IC3") (pin "78") (pinfunction "PC10_78") (pintype "bidirectional"))
      (node (ref "RN5") (pin "1") (pinfunction "1_1") (pintype "passive"))
    )
    (net (code "103") (name "/SD3") (class "Default")
      (node (ref "C16") (pin "P$8") (pinfunction "CD/D3_P$8") (pintype "bidirectional"))
      (node (ref "IC3") (pin "79") (pinfunction "PC11_79") (pintype "bidirectional"))
      (node (ref "RN5") (pin "2") (pinfunction "1_2") (pintype "passive"))
    )
    (net (code "104") (name "/SDA") (class "Default")
      (node (ref "IC3") (pin "47") (pinfunction "PB11_47") (pintype "bidirectional"))
      (node (ref "T1") (pin "E7") (pinfunction "P$7_E7") (pintype "bidirectional"))
    )
    (net (code "105") (name "/SDA2") (class "Default")
      (node (ref "IC3") (pin "96") (pinfunction "PB9_96") (pintype "bidirectional"))
      (node (ref "T1") (pin "E19") (pinfunction "P$19_E19") (pintype "bidirectional"))
    )
    (net (code "106") (name "/SDK") (class "Default")
      (node (ref "C16") (pin "P$5") (pinfunction "CLK_P$5") (pintype "bidirectional"))
      (node (ref "IC3") (pin "80") (pinfunction "PC12_80") (pintype "bidirectional"))
      (node (ref "RN1") (pin "6") (pinfunction "2_6") (pintype "passive"))
    )
    (net (code "107") (name "/SHA") (class "Default")
      (node (ref "C10") (pin "P$1") (pinfunction "SHLD_P$1") (pintype "passive"))
      (node (ref "C10") (pin "P$2") (pinfunction "SHLD_P$2") (pintype "passive"))
      (node (ref "C10") (pin "P$3") (pinfunction "SHLD_P$3") (pintype "passive"))
      (node (ref "C10") (pin "P$4") (pinfunction "SHLD_P$4") (pintype "passive"))
      (node (ref "C11") (pin "2") (pinfunction "2_2") (pintype "passive"))
    )
    (net (code "108") (name "/SI") (class "Default")
      (node (ref "IC3") (pin "54") (pinfunction "PB15_54") (pintype "bidirectional"))
      (node (ref "IC6") (pin "5") (pinfunction "SI_5") (pintype "bidirectional"))
    )
    (net (code "109") (name "/SO") (class "Default")
      (node (ref "IC3") (pin "53") (pinfunction "PB14_53") (pintype "bidirectional"))
      (node (ref "IC6") (pin "2") (pinfunction "SO_2") (pintype "bidirectional"))
    )
    (net (code "110") (name "/SPI{slash}SDA") (class "Default")
      (node (ref "C25") (pin "P$13") (pinfunction "P$13_P$13") (pintype "bidirectional"))
    )
    (net (code "111") (name "/SPI{slash}SDO") (class "Default")
      (node (ref "C25") (pin "P$14") (pinfunction "P$14_P$14") (pintype "bidirectional"))
    )
    (net (code "112") (name "/SWCLK") (class "Default")
      (node (ref "C34") (pin "2") (pinfunction "2_2") (pintype "bidirectional"))
      (node (ref "IC3") (pin "76") (pinfunction "PA14_76") (pintype "bidirectional"))
    )
    (net (code "113") (name "/SWDIO") (class "Default")
      (node (ref "C34") (pin "1") (pinfunction "1_1") (pintype "bidirectional"))
      (node (ref "IC3") (pin "72") (pinfunction "PA13_72") (pintype "bidirectional"))
    )
    (net (code "114") (name "/SWO") (class "Default")
      (node (ref "C34") (pin "3") (pinfunction "3_3") (pintype "bidirectional"))
      (node (ref "IC3") (pin "89") (pinfunction "PB3_89") (pintype "bidirectional"))
    )
    (net (code "115") (name "/TDI") (class "Default")
      (node (ref "C34") (pin "4") (pinfunction "4_4") (pintype "bidirectional"))
      (node (ref "IC3") (pin "77") (pinfunction "PA15_77") (pintype "bidirectional"))
    )
    (net (code "116") (name "/TX") (class "Default")
      (node (ref "C10") (pin "SBU1") (pinfunction "SBU1_SBU1") (pintype "bidirectional"))
      (node (ref "IC3") (pin "69") (pinfunction "PA10_69") (pintype "bidirectional"))
    )
    (net (code "117") (name "/VB1+") (class "Default")
      (node (ref "T1") (pin "E26") (pinfunction "P$26_E26") (pintype "bidirectional"))
      (node (ref "T1") (pin "E27") (pinfunction "P$27_E27") (pintype "bidirectional"))
      (node (ref "T1") (pin "E28") (pinfunction "P$28_E28") (pintype "bidirectional"))
    )
    (net (code "118") (name "/VB2+") (class "Default")
      (node (ref "T1") (pin "W26") (pinfunction "P$76_W26") (pintype "bidirectional"))
      (node (ref "T1") (pin "W27") (pinfunction "P$77_W27") (pintype "bidirectional"))
      (node (ref "T1") (pin "W28") (pinfunction "P$78_W28") (pintype "bidirectional"))
      (node (ref "T1") (pin "W29") (pinfunction "P$79_W29") (pintype "bidirectional"))
    )
    (net (code "119") (name "/VB3+") (class "Default")
      (node (ref "T1") (pin "E23") (pinfunction "P$23_E23") (pintype "bidirectional"))
      (node (ref "T1") (pin "E24") (pinfunction "P$24_E24") (pintype "bidirectional"))
      (node (ref "T1") (pin "E25") (pinfunction "P$25_E25") (pintype "bidirectional"))
    )
    (net (code "120") (name "/VB4+") (class "Default")
      (node (ref "T1") (pin "W22") (pinfunction "P$72_W22") (pintype "bidirectional"))
      (node (ref "T1") (pin "W23") (pinfunction "P$73_W23") (pintype "bidirectional"))
      (node (ref "T1") (pin "W24") (pinfunction "P$74_W24") (pintype "bidirectional"))
      (node (ref "T1") (pin "W25") (pinfunction "P$75_W25") (pintype "bidirectional"))
    )
    (net (code "121") (name "/VBAT") (class "Default")
      (node (ref "BT1") (pin "1") (pinfunction "+_1") (pintype "power_in"))
      (node (ref "C12") (pin "1") (pinfunction "1_1") (pintype "passive"))
      (node (ref "IC3") (pin "6") (pinfunction "VBAT_6") (pintype "bidirectional"))
    )
    (net (code "122") (name "/VBUSA") (class "Default")
      (node (ref "C10") (pin "VBUS@1") (pinfunction "VBUS_VBUS@1") (pintype "power_in"))
      (node (ref "C10") (pin "VBUS@2") (pinfunction "VBUS_VBUS@2") (pintype "power_in"))
      (node (ref "D1") (pin "A") (pinfunction "A_A") (pintype "passive"))
      (node (ref "IC1") (pin "5") (pinfunction "VBUS_5") (pintype "bidirectional"))
    )
    (net (code "123") (name "/VCC") (class "Default")
      (node (ref "T1") (pin "E4") (pinfunction "P$4_E4") (pintype "bidirectional"))
    )
    (net (code "124") (name "/VP") (class "Default")
      (node (ref "T1") (pin "E29") (pinfunction "P$29_E29") (pintype "bidirectional"))
    )
    (net (code "125") (name "/X+") (class "Default")
      (node (ref "C25") (pin "P$3") (pinfunction "P$3_P$3") (pintype "bidirectional"))
    )
    (net (code "126") (name "/X-") (class "Default")
      (node (ref "C25") (pin "P$4") (pinfunction "P$4_P$4") (pintype "bidirectional"))
    )
    (net (code "127") (name "/Y+") (class "Default")
      (node (ref "C25") (pin "P$1") (pinfunction "P$1_P$1") (pintype "bidirectional"))
    )
    (net (code "128") (name "/Y-") (class "Default")
      (node (ref "C25") (pin "P$2") (pinfunction "P$2_P$2") (pintype "bidirectional"))
    )
    (net (code "129") (name "/~{DCS}") (class "Default")
      (node (ref "C25") (pin "P$9") (pinfunction "P$9_P$9") (pintype "bidirectional"))
      (node (ref "IC3") (pin "88") (pinfunction "PD7_88") (pintype "bidirectional"))
    )
    (net (code "130") (name "/~{DOE}") (class "Default")
      (node (ref "C25") (pin "P$12") (pinfunction "P$12_P$12") (pintype "bidirectional"))
      (node (ref "IC3") (pin "85") (pinfunction "PD4_85") (pintype "bidirectional"))
    )
    (net (code "131") (name "/~{DWE}") (class "Default")
      (node (ref "C25") (pin "P$11") (pinfunction "P$11_P$11") (pintype "bidirectional"))
      (node (ref "IC3") (pin "86") (pinfunction "PD5_86") (pintype "bidirectional"))
    )
    (net (code "132") (name "/~{EN}") (class "Default")
      (node (ref "IC3") (pin "91") (pinfunction "PB5_91") (pintype "bidirectional"))
      (node (ref "Q6") (pin "1") (pinfunction "G_1") (pintype "passive"))
      (node (ref "T1") (pin "E39") (pinfunction "P$39_E39") (pintype "bidirectional"))
    )
    (net (code "133") (name "/~{HINT}") (class "Default")
      (node (ref "IC4") (pin "A5") (pinfunction "INT#_A5") (pintype "bidirectional"))
      (node (ref "T1") (pin "W7") (pinfunction "P$57_W7") (pintype "bidirectional"))
    )
    (net (code "134") (name "/~{INT}") (class "Default")
      (node (ref "IC3") (pin "84") (pinfunction "PD3_84") (pintype "bidirectional"))
      (node (ref "RN3") (pin "8") (pinfunction "2_8") (pintype "passive"))
      (node (ref "T1") (pin "W32") (pinfunction "P$82_W32") (pintype "bidirectional"))
    )
    (net (code "135") (name "/~{QSS}") (class "Default")
      (node (ref "IC3") (pin "92") (pinfunction "PB6_92") (pintype "bidirectional"))
      (node (ref "T1") (pin "W8") (pinfunction "P$58_W8") (pintype "bidirectional"))
    )
    (net (code "136") (name "/~{RESET}") (class "Default")
      (node (ref "C25") (pin "P$15") (pinfunction "P$15_P$15") (pintype "bidirectional"))
      (node (ref "IC3") (pin "90") (pinfunction "PB4_90") (pintype "bidirectional"))
      (node (ref "IC4") (pin "A4") (pinfunction "RESET#_A4") (pintype "bidirectional"))
      (node (ref "IC5") (pin "A4") (pinfunction "RESET#_A4") (pintype "bidirectional"))
      (node (ref "T1") (pin "E38") (pinfunction "P$38_E38") (pintype "bidirectional"))
    )
    (net (code "137") (name "/~{SRST}") (class "Default")
      (node (ref "C15") (pin "2") (pinfunction "2_2") (pintype "passive"))
      (node (ref "C34") (pin "5") (pinfunction "5_5") (pintype "bidirectional"))
      (node (ref "IC3") (pin "14") (pinfunction "NRST_14") (pintype "bidirectional"))
      (node (ref "RN3") (pin "6") (pinfunction "2_6") (pintype "passive"))
    )
    (net (code "138") (name "/~{SS}") (class "Default")
      (node (ref "IC3") (pin "51") (pinfunction "PB12_51") (pintype "bidirectional"))
      (node (ref "IC6") (pin "1") (pinfunction "CS_1") (pintype "input"))
    )
    (net (code "139") (name "GND") (class "Default")
      (node (ref "BT1") (pin "2") (pinfunction "-_2") (pintype "power_in"))
      (node (ref "C1") (pin "2") (pinfunction "2_2") (pintype "passive"))
      (node (ref "C10") (pin "GND@1") (pinfunction "GND_GND@1") (pintype "power_in"))
      (node (ref "C10") (pin "GND@2") (pinfunction "GND_GND@2") (pintype "power_in"))
      (node (ref "C11") (pin "1") (pinfunction "1_1") (pintype "passive"))
      (node (ref "C12") (pin "2") (pinfunction "2_2") (pintype "passive"))
      (node (ref "C15") (pin "1") (pinfunction "1_1") (pintype "passive"))
      (node (ref "C16") (pin "P$10") (pinfunction "SH_P$10") (pintype "passive"))
      (node (ref "C16") (pin "P$11") (pinfunction "SH_P$11") (pintype "passive"))
      (node (ref "C16") (pin "P$12") (pinfunction "SH_P$12") (pintype "passive"))
      (node (ref "C16") (pin "P$13") (pinfunction "SH_P$13") (pintype "passive"))
      (node (ref "C16") (pin "P$4") (pinfunction "VSS_P$4") (pintype "power_in"))
      (node (ref "C17") (pin "1") (pinfunction "1_1") (pintype "passive"))
      (node (ref "C18") (pin "1") (pinfunction "1_1") (pintype "passive"))
      (node (ref "C19") (pin "2") (pinfunction "2_2") (pintype "passive"))
      (node (ref "C2") (pin "1") (pinfunction "1_1") (pintype "passive"))
      (node (ref "C20") (pin "2") (pinfunction "2_2") (pintype "passive"))
      (node (ref "C21") (pin "2") (pinfunction "2_2") (pintype "passive"))
      (node (ref "C22") (pin "2") (pinfunction "2_2") (pintype "passive"))
      (node (ref "C23") (pin "2") (pinfunction "2_2") (pintype "passive"))
      (node (ref "C24") (pin "2") (pinfunction "2_2") (pintype "passive"))
      (node (ref "C25") (pin "P$16") (pinfunction "P$16_P$16") (pintype "bidirectional"))
      (node (ref "C25") (pin "P$37") (pinfunction "P$37_P$37") (pintype "bidirectional"))
      (node (ref "C25") (pin "P$38") (pinfunction "P$38_P$38") (pintype "bidirectional"))
      (node (ref "C25") (pin "P$40") (pinfunction "P$40_P$40") (pintype "bidirectional"))
      (node (ref "C25") (pin "P$5") (pinfunction "P$5_P$5") (pintype "bidirectional"))
      (node (ref "C26") (pin "1") (pinfunction "1_1") (pintype "passive"))
      (node (ref "C27") (pin "1") (pinfunction "1_1") (pintype "passive"))
      (node (ref "C28") (pin "2") (pinfunction "2_2") (pintype "passive"))
      (node (ref "C29") (pin "1") (pinfunction "1_1") (pintype "passive"))
      (node (ref "C3") (pin "1") (pinfunction "1_1") (pintype "passive"))
      (node (ref "C30") (pin "1") (pinfunction "1_1") (pintype "passive"))
      (node (ref "C31") (pin "1") (pinfunction "1_1") (pintype "passive"))
      (node (ref "C32") (pin "2") (pinfunction "2_2") (pintype "passive"))
      (node (ref "C33") (pin "1") (pinfunction "1_1") (pintype "passive"))
      (node (ref "C34") (pin "6") (pinfunction "6_6") (pintype "bidirectional"))
      (node (ref "C34") (pin "8") (pinfunction "8_8") (pintype "bidirectional"))
      (node (ref "C34") (pin "9") (pinfunction "9_9") (pintype "bidirectional"))
      (node (ref "C35") (pin "P$10") (pinfunction "SH_P$10") (pintype "passive"))
      (node (ref "C35") (pin "P$11") (pinfunction "SH_P$11") (pintype "passive"))
      (node (ref "C35") (pin "P$12") (pinfunction "SH_P$12") (pintype "passive"))
      (node (ref "C35") (pin "P$13") (pinfunction "SH_P$13") (pintype "passive"))
      (node (ref "C35") (pin "P$4") (pinfunction "VSS_P$4") (pintype "power_in"))
      (node (ref "C36") (pin "P$10") (pinfunction "SH_P$10") (pintype "passive"))
      (node (ref "C36") (pin "P$11") (pinfunction "SH_P$11") (pintype "passive"))
      (node (ref "C36") (pin "P$12") (pinfunction "SH_P$12") (pintype "passive"))
      (node (ref "C36") (pin "P$13") (pinfunction "SH_P$13") (pintype "passive"))
      (node (ref "C36") (pin "P$4") (pinfunction "VSS_P$4") (pintype "power_in"))
      (node (ref "C38") (pin "P$10") (pinfunction "SH_P$10") (pintype "passive"))
      (node (ref "C38") (pin "P$11") (pinfunction "SH_P$11") (pintype "passive"))
      (node (ref "C38") (pin "P$12") (pinfunction "SH_P$12") (pintype "passive"))
      (node (ref "C38") (pin "P$13") (pinfunction "SH_P$13") (pintype "passive"))
      (node (ref "C38") (pin "P$4") (pinfunction "VSS_P$4") (pintype "power_in"))
      (node (ref "C4") (pin "1") (pinfunction "1_1") (pintype "passive"))
      (node (ref "C41") (pin "P$10") (pinfunction "SH_P$10") (pintype "passive"))
      (node (ref "C41") (pin "P$11") (pinfunction "SH_P$11") (pintype "passive"))
      (node (ref "C41") (pin "P$12") (pinfunction "SH_P$12") (pintype "passive"))
      (node (ref "C41") (pin "P$13") (pinfunction "SH_P$13") (pintype "passive"))
      (node (ref "C41") (pin "P$4") (pinfunction "VSS_P$4") (pintype "power_in"))
      (node (ref "C5") (pin "1") (pinfunction "1_1") (pintype "passive"))
      (node (ref "C6") (pin "1") (pinfunction "1_1") (pintype "passive"))
      (node (ref "C7") (pin "1") (pinfunction "1_1") (pintype "passive"))
      (node (ref "C8") (pin "1") (pinfunction "1_1") (pintype "passive"))
      (node (ref "C9") (pin "2") (pinfunction "2_2") (pintype "passive"))
      (node (ref "IC1") (pin "2") (pinfunction "GND_2") (pintype "bidirectional"))
      (node (ref "IC3") (pin "10") (pinfunction "VSS_1_10") (pintype "bidirectional"))
      (node (ref "IC3") (pin "19") (pinfunction "VSSA_19") (pintype "bidirectional"))
      (node (ref "IC3") (pin "26") (pinfunction "VSS_2_26") (pintype "bidirectional"))
      (node (ref "IC3") (pin "49") (pinfunction "VSS_3_49") (pintype "bidirectional"))
      (node (ref "IC3") (pin "74") (pinfunction "VSS_4_74") (pintype "bidirectional"))
      (node (ref "IC3") (pin "99") (pinfunction "VSS_5_99") (pintype "bidirectional"))
      (node (ref "IC4") (pin "B3") (pinfunction "VSS_B3") (pintype "bidirectional"))
      (node (ref "IC4") (pin "C1") (pinfunction "VSSQ_1_C1") (pintype "bidirectional"))
      (node (ref "IC4") (pin "E5") (pinfunction "VSSQ_2_E5") (pintype "bidirectional"))
      (node (ref "IC5") (pin "B3") (pinfunction "VSS_B3") (pintype "bidirectional"))
      (node (ref "IC5") (pin "C1") (pinfunction "VSSQ_1_C1") (pintype "bidirectional"))
      (node (ref "IC5") (pin "E5") (pinfunction "VSSQ_2_E5") (pintype "bidirectional"))
      (node (ref "IC6") (pin "4") (pinfunction "GND_4") (pintype "power_in"))
      (node (ref "RN1") (pin "1") (pinfunction "1_1") (pintype "passive"))
      (node (ref "RN1") (pin "2") (pinfunction "1_2") (pintype "passive"))
      (node (ref "RN3") (pin "2") (pinfunction "1_2") (pintype "passive"))
      (node (ref "RN6") (pin "6") (pinfunction "2_6") (pintype "passive"))
      (node (ref "RN8") (pin "2") (pinfunction "1_2") (pintype "passive"))
      (node (ref "RN8") (pin "3") (pinfunction "1_3") (pintype "passive"))
      (node (ref "RN8") (pin "4") (pinfunction "1_4") (pintype "passive"))
      (node (ref "T1") (pin "E1") (pinfunction "P$1_E1") (pintype "bidirectional"))
      (node (ref "T1") (pin "E2") (pinfunction "P$2_E2") (pintype "bidirectional"))
      (node (ref "T1") (pin "E3") (pinfunction "P$3_E3") (pintype "bidirectional"))
      (node (ref "T1") (pin "E48") (pinfunction "P$48_E48") (pintype "bidirectional"))
      (node (ref "T1") (pin "E49") (pinfunction "P$49_E49") (pintype "bidirectional"))
      (node (ref "T1") (pin "E50") (pinfunction "P$50_E50") (pintype "bidirectional"))
      (node (ref "T1") (pin "W1") (pinfunction "P$51_W1") (pintype "bidirectional"))
      (node (ref "T1") (pin "W2") (pinfunction "P$52_W2") (pintype "bidirectional"))
      (node (ref "T1") (pin "W3") (pinfunction "P$53_W3") (pintype "bidirectional"))
      (node (ref "T1") (pin "W4") (pinfunction "P$54_W4") (pintype "bidirectional"))
      (node (ref "T1") (pin "W47") (pinfunction "P$97_W47") (pintype "bidirectional"))
      (node (ref "T1") (pin "W48") (pinfunction "P$98_W48") (pintype "bidirectional"))
      (node (ref "T1") (pin "W49") (pinfunction "P$99_W49") (pintype "bidirectional"))
      (node (ref "T1") (pin "W50") (pinfunction "P$100_W50") (pintype "bidirectional"))
      (node (ref "X2") (pin "2") (pinfunction "GND_2") (pintype "power_in"))
      (node (ref "X2") (pin "4") (pinfunction "GND_4") (pintype "passive"))
    )
    (net (code "140") (name "Net-(IC3-PC14-OSC32_IN)") (class "Default")
      (node (ref "C3") (pin "2") (pinfunction "2_2") (pintype "passive"))
      (node (ref "IC3") (pin "8") (pinfunction "PC14-OSC32_IN_8") (pintype "bidirectional"))
      (node (ref "X1") (pin "P$2") (pinfunction "X2_P$2") (pintype "passive"))
    )
    (net (code "141") (name "Net-(IC3-PC15-OSC32_OUT)") (class "Default")
      (node (ref "C4") (pin "2") (pinfunction "2_2") (pintype "passive"))
      (node (ref "IC3") (pin "9") (pinfunction "PC15-OSC32_OUT_9") (pintype "bidirectional"))
      (node (ref "X1") (pin "P$1") (pinfunction "X1_P$1") (pintype "passive"))
    )
    (net (code "142") (name "Net-(IC3-PH0-OSC_IN)") (class "Default")
      (node (ref "C5") (pin "2") (pinfunction "2_2") (pintype "passive"))
      (node (ref "IC3") (pin "12") (pinfunction "PH0-OSC_IN_12") (pintype "bidirectional"))
      (node (ref "X2") (pin "1") (pinfunction "X1_1") (pintype "passive"))
    )
    (net (code "143") (name "Net-(IC3-PH1-OSC_OUT)") (class "Default")
      (node (ref "C6") (pin "2") (pinfunction "2_2") (pintype "passive"))
      (node (ref "IC3") (pin "13") (pinfunction "PH1-OSC_OUT_13") (pintype "bidirectional"))
      (node (ref "X2") (pin "3") (pinfunction "X2_3") (pintype "passive"))
    )
    (net (code "144") (name "Net-(IC3-VCAP1)") (class "Default")
      (node (ref "C17") (pin "2") (pinfunction "2_2") (pintype "passive"))
      (node (ref "IC3") (pin "48") (pinfunction "VCAP1_48") (pintype "bidirectional"))
    )
    (net (code "145") (name "Net-(IC3-VCAP2)") (class "Default")
      (node (ref "C19") (pin "1") (pinfunction "1_1") (pintype "passive"))
      (node (ref "IC3") (pin "73") (pinfunction "VCAP2_73") (pintype "bidirectional"))
    )
    (net (code "146") (name "Net-(IC3-VDDA)") (class "Default")
      (node (ref "C9") (pin "1") (pinfunction "1_1") (pintype "passive"))
      (node (ref "IC3") (pin "20") (pinfunction "VREF+_20") (pintype "bidirectional"))
      (node (ref "IC3") (pin "21") (pinfunction "VDDA_21") (pintype "bidirectional"))
      (node (ref "R1") (pin "1") (pinfunction "1_1") (pintype "passive"))
    )
    (net (code "147") (name "Net-(L1-BC)") (class "Default")
      (node (ref "L1") (pin "B") (pinfunction "BC_B") (pintype "bidirectional"))
      (node (ref "RN6") (pin "4") (pinfunction "1_4") (pintype "passive"))
    )
    (net (code "148") (name "Net-(L1-GC)") (class "Default")
      (node (ref "L1") (pin "G") (pinfunction "GC_G") (pintype "bidirectional"))
      (node (ref "RN6") (pin "3") (pinfunction "1_3") (pintype "passive"))
    )
    (net (code "149") (name "Net-(L1-RC)") (class "Default")
      (node (ref "L1") (pin "R") (pinfunction "RC_R") (pintype "bidirectional"))
      (node (ref "RN6") (pin "2") (pinfunction "1_2") (pintype "passive"))
    )
    (net (code "150") (name "unconnected-(C16-CD-PadP$1)") (class "Default")
      (node (ref "C16") (pin "P$1") (pinfunction "CD_P$1") (pintype "bidirectional"))
    )
    (net (code "151") (name "unconnected-(C34-Pad7)") (class "Default")
      (node (ref "C34") (pin "7") (pinfunction "7_7") (pintype "bidirectional"))
    )
    (net (code "152") (name "unconnected-(IC1-I{slash}O1_1-Pad1)") (class "Default")
      (node (ref "IC1") (pin "1") (pinfunction "I/O1_1_1") (pintype "bidirectional"))
    )
    (net (code "153") (name "unconnected-(IC1-I{slash}O2_1-Pad3)") (class "Default")
      (node (ref "IC1") (pin "3") (pinfunction "I/O2_1_3") (pintype "bidirectional"))
    )
    (net (code "154") (name "unconnected-(IC4-CK#-PadB1)") (class "Default")
      (node (ref "IC4") (pin "B1") (pinfunction "CK#_B1") (pintype "bidirectional"))
    )
    (net (code "155") (name "unconnected-(IC4-DNU-PadA3)") (class "Default")
      (node (ref "IC4") (pin "A3") (pinfunction "DNU_A3") (pintype "bidirectional"))
    )
    (net (code "156") (name "unconnected-(IC4-PSC#-PadC5)") (class "Default")
      (node (ref "IC4") (pin "C5") (pinfunction "PSC#_C5") (pintype "bidirectional"))
    )
    (net (code "157") (name "unconnected-(IC4-PSC-PadB5)") (class "Default")
      (node (ref "IC4") (pin "B5") (pinfunction "PSC_B5") (pintype "bidirectional"))
    )
    (net (code "158") (name "unconnected-(IC4-RSTO#-PadA2)") (class "Default")
      (node (ref "IC4") (pin "A2") (pinfunction "RSTO#_A2") (pintype "bidirectional"))
    )
    (net (code "159") (name "unconnected-(IC5-CK#-PadB1)") (class "Default")
      (node (ref "IC5") (pin "B1") (pinfunction "CK#_B1") (pintype "bidirectional"))
    )
    (net (code "160") (name "unconnected-(IC5-RFU_1-PadA2)") (class "Default")
      (node (ref "IC5") (pin "A2") (pinfunction "RFU_1_A2") (pintype "bidirectional"))
    )
    (net (code "161") (name "unconnected-(IC5-RFU_2-PadA5)") (class "Default")
      (node (ref "IC5") (pin "A5") (pinfunction "RFU_2_A5") (pintype "bidirectional"))
    )
    (net (code "162") (name "unconnected-(IC5-RFU_3-PadB5)") (class "Default")
      (node (ref "IC5") (pin "B5") (pinfunction "RFU_3_B5") (pintype "bidirectional"))
    )
    (net (code "163") (name "unconnected-(IC5-RFU_4-PadC2)") (class "Default")
      (node (ref "IC5") (pin "C2") (pinfunction "RFU_4_C2") (pintype "bidirectional"))
    )
    (net (code "164") (name "unconnected-(IC5-RFU_5-PadC5)") (class "Default")
      (node (ref "IC5") (pin "C5") (pinfunction "RFU_5_C5") (pintype "bidirectional"))
    )
    (net (code "165") (name "unconnected-(RN3D-1-Pad4)") (class "Default")
      (node (ref "RN3") (pin "4") (pinfunction "1_4") (pintype "passive"))
    )
    (net (code "166") (name "unconnected-(RN3D-2-Pad5)") (class "Default")
      (node (ref "RN3") (pin "5") (pinfunction "2_5") (pintype "passive"))
    )
    (net (code "167") (name "unconnected-(RN8-Pad1)") (class "Default")
      (node (ref "RN8") (pin "1") (pinfunction "1_1") (pintype "passive"))
    )
    (net (code "168") (name "unconnected-(RN8A-2-Pad8)") (class "Default")
      (node (ref "RN8") (pin "8") (pinfunction "2_8") (pintype "passive"))
    )
  )
)
